# main.net
KiCad netlist of a schematic drawn in EAGLE
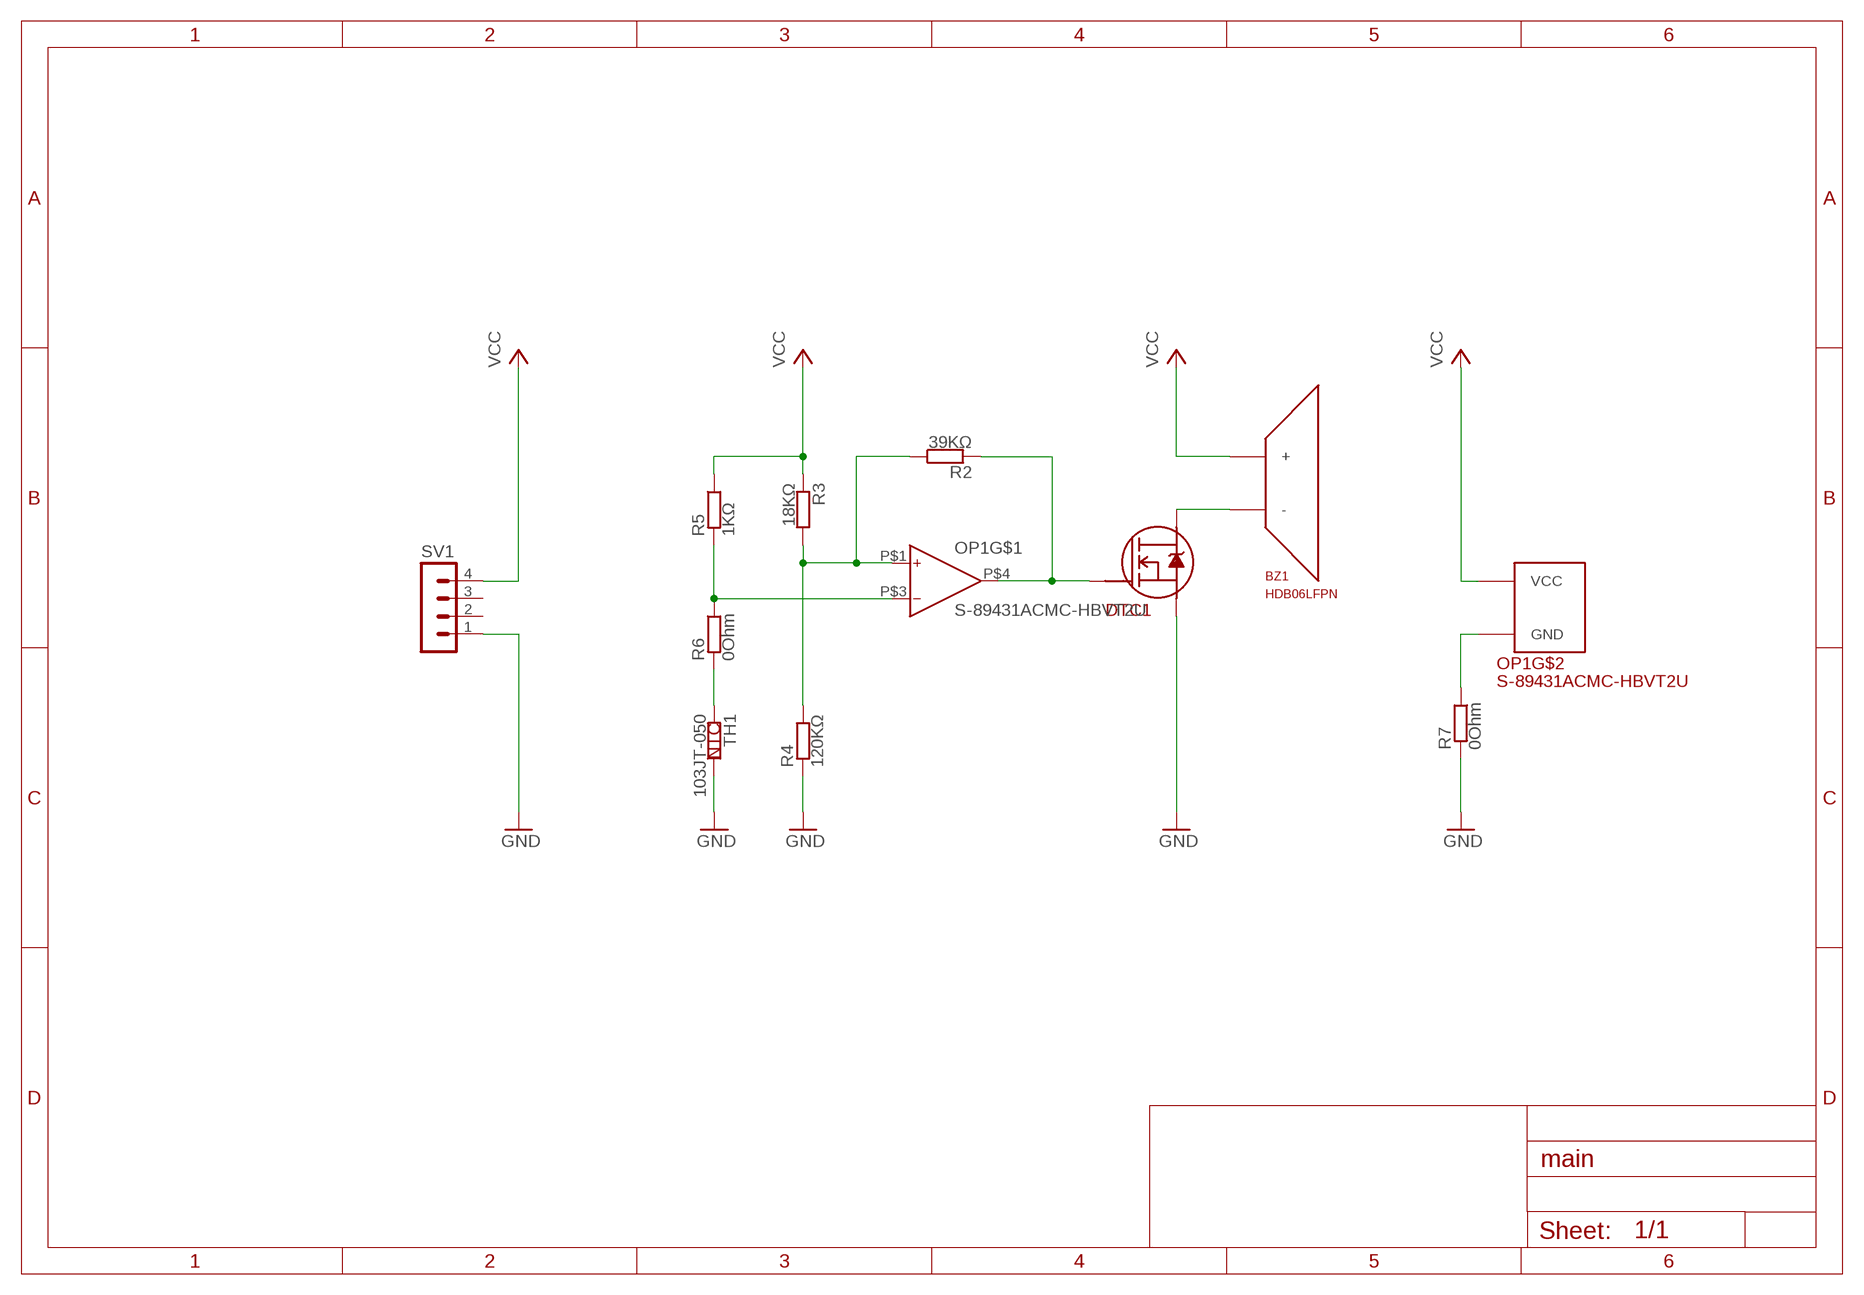
[diagram p0: schematic, sheet 1]

(export (version "E")
  (design (tool "Eeschema 10.0.6"))
  (components
    (comp (ref "BZ1")
      (value "HDB06LFPN")
      (footprint "eagle-import:HDB06FLPN")
      (libsource (lib "eagle-import") (part "HDB06LFPN"))
    )
    (comp (ref "DTC1")
      (value "RT1P137P")
      (footprint "eagle-import:SC-62")
      (libsource (lib "eagle-import") (part "RT1P137P"))
    )
    (comp (ref "OP1")
      (value "S-89431ACMC-HBVT2U")
      (footprint "eagle-import:SOT-23-5")
      (libsource (lib "eagle-import") (part "S-89431ACMC-HBVT2U"))
    )
    (comp (ref "R2")
      (value "39KΩ")
      (footprint "eagle-import:MF1_4")
      (libsource (lib "eagle-import") (part "1/4W_RESISTER"))
    )
    (comp (ref "R3")
      (value "18KΩ")
      (footprint "eagle-import:MF1_4")
      (libsource (lib "eagle-import") (part "1/4W_RESISTER"))
    )
    (comp (ref "R4")
      (value "120KΩ")
      (footprint "eagle-import:MF1_4")
      (libsource (lib "eagle-import") (part "1/4W_RESISTER"))
    )
    (comp (ref "R5")
      (value "1KΩ")
      (footprint "eagle-import:MF1_4")
      (libsource (lib "eagle-import") (part "1/4W_RESISTER"))
    )
    (comp (ref "R6")
      (value "0Ohm")
      (footprint "eagle-import:MF1_4")
      (libsource (lib "eagle-import") (part "1/4W_RESISTER"))
    )
    (comp (ref "R7")
      (value "0Ohm")
      (footprint "eagle-import:MF1_4")
      (libsource (lib "eagle-import") (part "1/4W_RESISTER"))
    )
    (comp (ref "SV1")
      (value "MA04-1")
      (footprint "eagle-import:MA04-1")
      (libsource (lib "eagle-import") (part "MA04-1"))
    )
    (comp (ref "TH1")
      (value "103JT-050")
      (footprint "eagle-import:JT-W")
      (libsource (lib "eagle-import") (part "103JT-050"))
    )
  )
  (nets
    (net (code "1") (name "GND") (class "Default")
      (node (ref "DTC1") (pin "E") (pinfunction "S_E") (pintype "bidirectional"))
      (node (ref "R4") (pin "P$2") (pinfunction "2_P$2") (pintype "passive"))
      (node (ref "R7") (pin "P$2") (pinfunction "2_P$2") (pintype "passive"))
      (node (ref "SV1") (pin "1") (pinfunction "1_1") (pintype "passive"))
      (node (ref "TH1") (pin "P$1") (pinfunction "1_P$1") (pintype "passive"))
    )
    (net (code "2") (name "Net-(BZ1--)") (class "Default")
      (node (ref "BZ1") (pin "P$2") (pinfunction "-_P$2") (pintype "bidirectional"))
      (node (ref "DTC1") (pin "C1") (pinfunction "D_C1") (pintype "bidirectional"))
      (node (ref "DTC1") (pin "C2") (pinfunction "D_C2") (pintype "bidirectional"))
    )
    (net (code "3") (name "Net-(DTC1-G)") (class "Default")
      (node (ref "DTC1") (pin "B") (pinfunction "G_B") (pintype "bidirectional"))
      (node (ref "OP1") (pin "P$4") (pinfunction "OUT_P$4") (pintype "output"))
      (node (ref "R2") (pin "P$2") (pinfunction "2_P$2") (pintype "passive"))
    )
    (net (code "4") (name "Net-(OP1A-IN+)") (class "Default")
      (node (ref "OP1") (pin "P$1") (pinfunction "IN+_P$1") (pintype "input"))
      (node (ref "R2") (pin "P$1") (pinfunction "1_P$1") (pintype "passive"))
      (node (ref "R3") (pin "P$1") (pinfunction "1_P$1") (pintype "passive"))
      (node (ref "R4") (pin "P$1") (pinfunction "1_P$1") (pintype "passive"))
    )
    (net (code "5") (name "Net-(OP1A-IN-)") (class "Default")
      (node (ref "OP1") (pin "P$3") (pinfunction "IN-_P$3") (pintype "input"))
      (node (ref "R5") (pin "P$2") (pinfunction "2_P$2") (pintype "passive"))
      (node (ref "R6") (pin "P$1") (pinfunction "1_P$1") (pintype "passive"))
    )
    (net (code "6") (name "Net-(OP1B-GND)") (class "Default")
      (node (ref "OP1") (pin "P$2") (pinfunction "GND_P$2") (pintype "bidirectional"))
      (node (ref "R7") (pin "P$1") (pinfunction "1_P$1") (pintype "passive"))
    )
    (net (code "7") (name "Net-(R6-2)") (class "Default")
      (node (ref "R6") (pin "P$2") (pinfunction "2_P$2") (pintype "passive"))
      (node (ref "TH1") (pin "P$2") (pinfunction "2_P$2") (pintype "passive"))
    )
    (net (code "8") (name "VCC") (class "Default")
      (node (ref "BZ1") (pin "P$1") (pinfunction "+_P$1") (pintype "bidirectional"))
      (node (ref "OP1") (pin "P$5") (pinfunction "VCC_P$5") (pintype "bidirectional"))
      (node (ref "R3") (pin "P$2") (pinfunction "2_P$2") (pintype "passive"))
      (node (ref "R5") (pin "P$1") (pinfunction "1_P$1") (pintype "passive"))
      (node (ref "SV1") (pin "4") (pinfunction "4_4") (pintype "passive"))
    )
    (net (code "9") (name "unconnected-(SV1-Pad2)") (class "Default")
      (node (ref "SV1") (pin "2") (pinfunction "2_2") (pintype "passive"))
    )
    (net (code "10") (name "unconnected-(SV1-Pad3)") (class "Default")
      (node (ref "SV1") (pin "3") (pinfunction "3_3") (pintype "passive"))
    )
  )
)
